# IO_Module.net
KiCad netlist of a schematic drawn in EAGLE
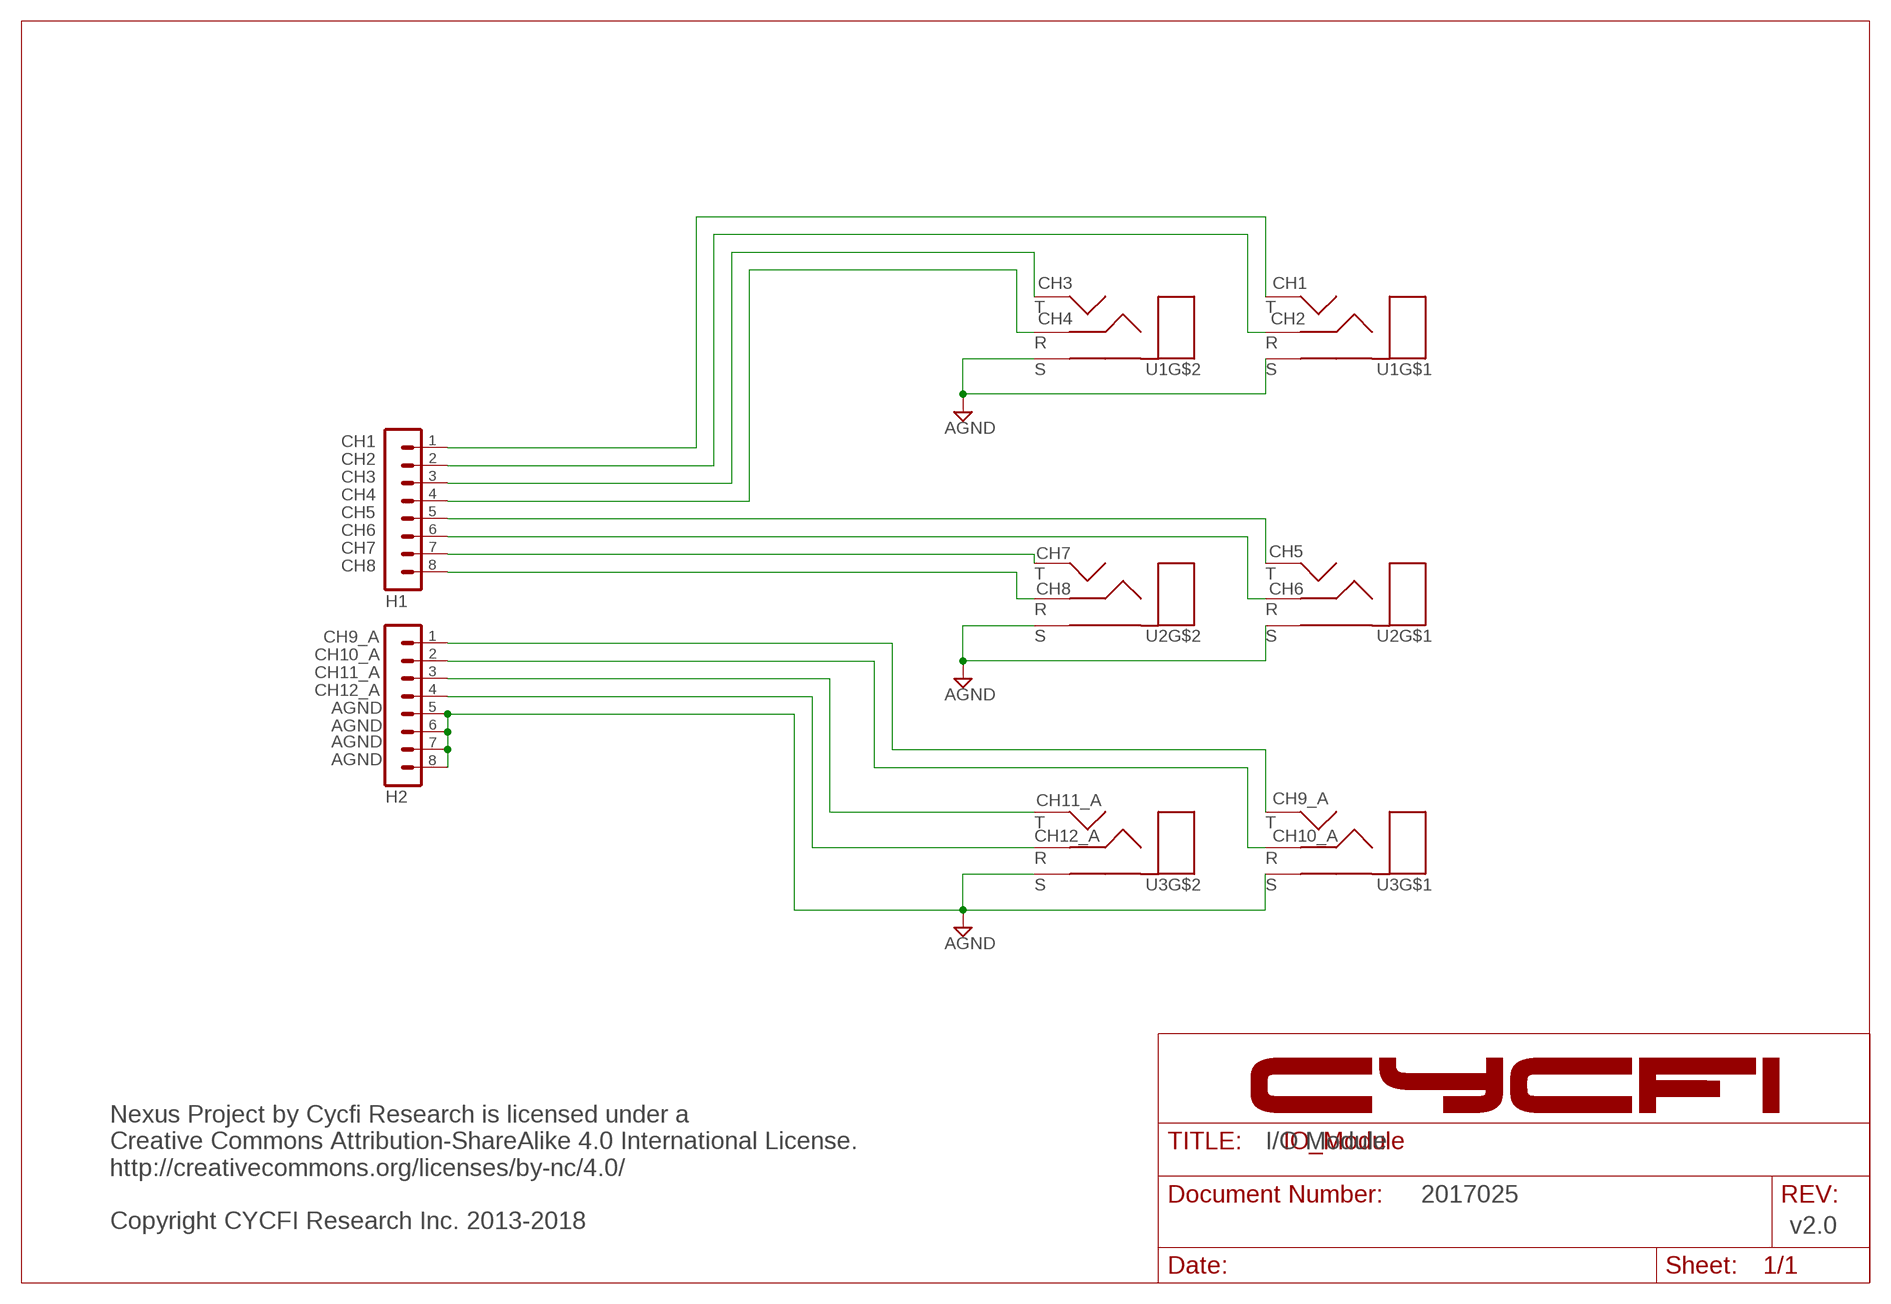
[diagram p0: schematic, sheet 1]

(export (version "E")
  (design (tool "Eeschema 10.0.6"))
  (components
    (comp (ref "H1")
      (value "MA08-1")
      (footprint "eagle-import:MA08-1")
      (libsource (lib "eagle-import") (part "MA08-1"))
    )
    (comp (ref "H2")
      (value "MA08-1")
      (footprint "eagle-import:MA08-1")
      (libsource (lib "eagle-import") (part "MA08-1"))
    )
    (comp (ref "U1")
      (value "AGND")
      (footprint "eagle-import:NSJ12HC")
      (libsource (lib "eagle-import") (part "NSJ12HC"))
    )
    (comp (ref "U2")
      (value "AGND")
      (footprint "eagle-import:NSJ12HC")
      (libsource (lib "eagle-import") (part "NSJ12HC"))
    )
    (comp (ref "U3")
      (value "AGND")
      (footprint "eagle-import:NSJ12HC")
      (libsource (lib "eagle-import") (part "NSJ12HC"))
    )
  )
  (nets
    (net (code "1") (name "/AGND") (class "Default")
      (node (ref "H2") (pin "5") (pinfunction "5_5") (pintype "passive"))
      (node (ref "H2") (pin "6") (pinfunction "6_6") (pintype "passive"))
      (node (ref "H2") (pin "7") (pinfunction "7_7") (pintype "passive"))
      (node (ref "H2") (pin "8") (pinfunction "8_8") (pintype "passive"))
      (node (ref "U1") (pin "G") (pinfunction "DGND_G") (pintype "power_in"))
      (node (ref "U1") (pin "SB") (pinfunction "S_SB") (pintype "bidirectional"))
      (node (ref "U1") (pin "ST") (pinfunction "S_ST") (pintype "bidirectional"))
      (node (ref "U2") (pin "G") (pinfunction "DGND_G") (pintype "power_in"))
      (node (ref "U2") (pin "SB") (pinfunction "S_SB") (pintype "bidirectional"))
      (node (ref "U2") (pin "ST") (pinfunction "S_ST") (pintype "bidirectional"))
      (node (ref "U3") (pin "G") (pinfunction "DGND_G") (pintype "power_in"))
      (node (ref "U3") (pin "SB") (pinfunction "S_SB") (pintype "bidirectional"))
      (node (ref "U3") (pin "ST") (pinfunction "S_ST") (pintype "bidirectional"))
    )
    (net (code "2") (name "Net-(U1A-R)") (class "Default")
      (node (ref "H1") (pin "2") (pinfunction "2_2") (pintype "passive"))
      (node (ref "U1") (pin "RT") (pinfunction "R_RT") (pintype "bidirectional"))
    )
    (net (code "3") (name "Net-(U1A-T)") (class "Default")
      (node (ref "H1") (pin "1") (pinfunction "1_1") (pintype "passive"))
      (node (ref "U1") (pin "TT") (pinfunction "T_TT") (pintype "bidirectional"))
    )
    (net (code "4") (name "Net-(U1B-R)") (class "Default")
      (node (ref "H1") (pin "4") (pinfunction "4_4") (pintype "passive"))
      (node (ref "U1") (pin "RB") (pinfunction "R_RB") (pintype "bidirectional"))
    )
    (net (code "5") (name "Net-(U1B-T)") (class "Default")
      (node (ref "H1") (pin "3") (pinfunction "3_3") (pintype "passive"))
      (node (ref "U1") (pin "TB") (pinfunction "T_TB") (pintype "bidirectional"))
    )
    (net (code "6") (name "Net-(U2A-R)") (class "Default")
      (node (ref "H1") (pin "6") (pinfunction "6_6") (pintype "passive"))
      (node (ref "U2") (pin "RT") (pinfunction "R_RT") (pintype "bidirectional"))
    )
    (net (code "7") (name "Net-(U2A-T)") (class "Default")
      (node (ref "H1") (pin "5") (pinfunction "5_5") (pintype "passive"))
      (node (ref "U2") (pin "TT") (pinfunction "T_TT") (pintype "bidirectional"))
    )
    (net (code "8") (name "Net-(U2B-R)") (class "Default")
      (node (ref "H1") (pin "8") (pinfunction "8_8") (pintype "passive"))
      (node (ref "U2") (pin "RB") (pinfunction "R_RB") (pintype "bidirectional"))
    )
    (net (code "9") (name "Net-(U2B-T)") (class "Default")
      (node (ref "H1") (pin "7") (pinfunction "7_7") (pintype "passive"))
      (node (ref "U2") (pin "TB") (pinfunction "T_TB") (pintype "bidirectional"))
    )
    (net (code "10") (name "Net-(U3A-R)") (class "Default")
      (node (ref "H2") (pin "2") (pinfunction "2_2") (pintype "passive"))
      (node (ref "U3") (pin "RT") (pinfunction "R_RT") (pintype "bidirectional"))
    )
    (net (code "11") (name "Net-(U3A-T)") (class "Default")
      (node (ref "H2") (pin "1") (pinfunction "1_1") (pintype "passive"))
      (node (ref "U3") (pin "TT") (pinfunction "T_TT") (pintype "bidirectional"))
    )
    (net (code "12") (name "Net-(U3B-R)") (class "Default")
      (node (ref "H2") (pin "4") (pinfunction "4_4") (pintype "passive"))
      (node (ref "U3") (pin "RB") (pinfunction "R_RB") (pintype "bidirectional"))
    )
    (net (code "13") (name "Net-(U3B-T)") (class "Default")
      (node (ref "H2") (pin "3") (pinfunction "3_3") (pintype "passive"))
      (node (ref "U3") (pin "TB") (pinfunction "T_TB") (pintype "bidirectional"))
    )
  )
)
